# 10_-FLASH_SD.net
KiCad netlist of a schematic drawn in Altium Designer
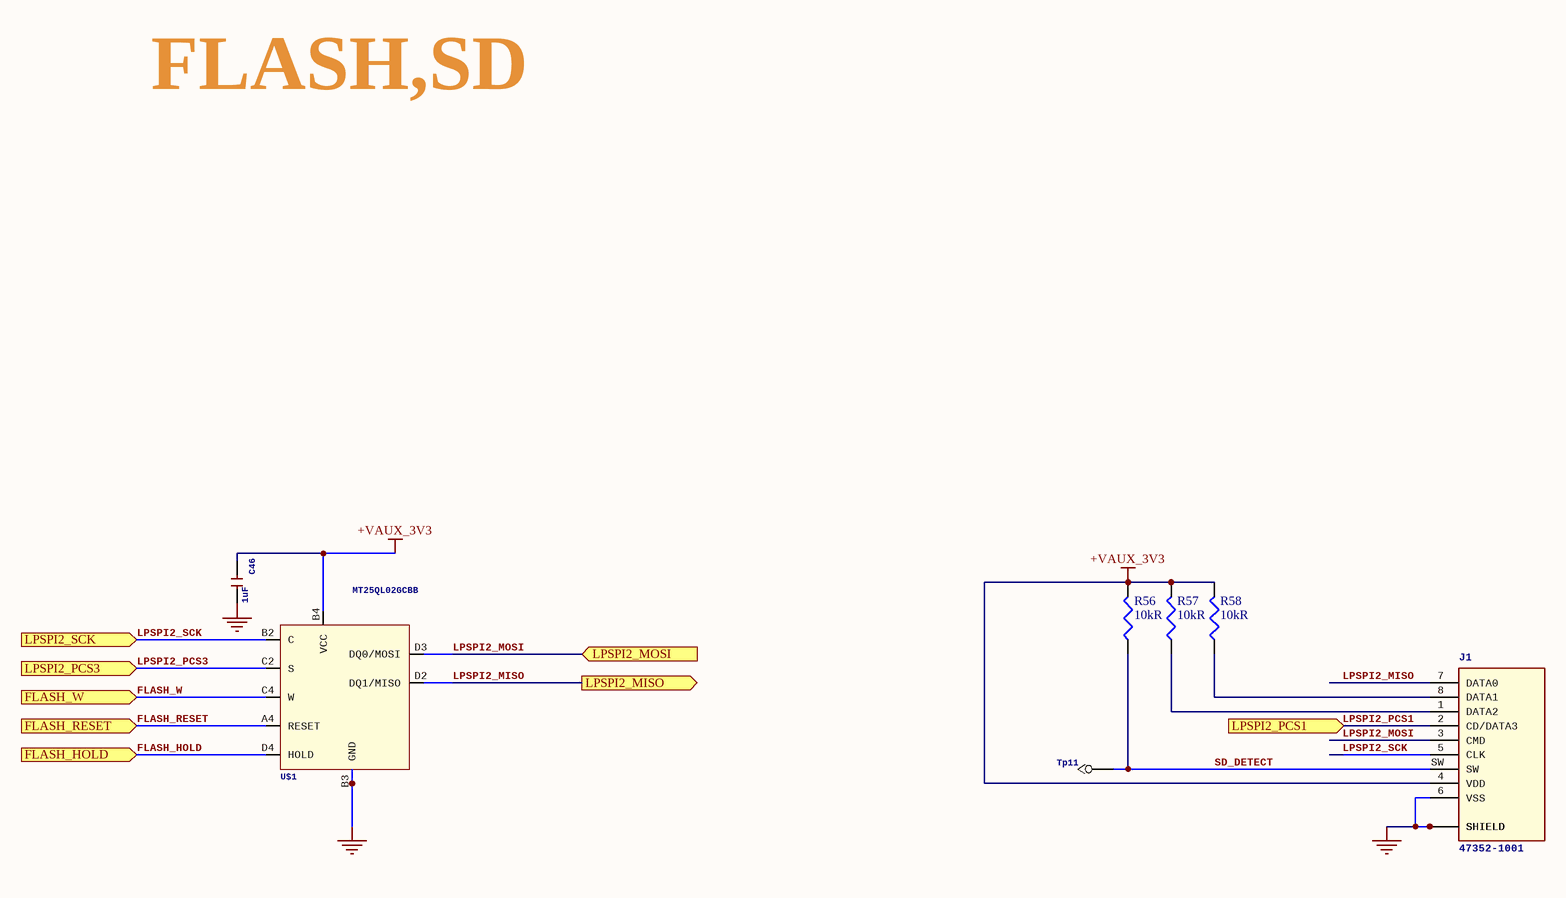
[diagram p0: [10]-FLASH,SD.SchDoc]

(export (version "E")
  (design (tool "Eeschema 10.0.6"))
  (components
    (comp (ref "C46")
      (value "1uF")
      (footprint "C0805")
      (description "302010165")
      (fields (field (name "MPN") "CC0805KRX7R9BB104") (field (name "LIBRARYNAME") "Seeed-Capacitor"))
      (libsource (lib "Seeed-Capacitor") (part "CERAMIC-100NF-50V-10%-X7R(0805)"))
    )
    (comp (ref "J1")
      (value "47352-1001")
      (footprint "MOLEX_47352-1001")
      (fields (field (name "MF") "Molex"))
      (libsource (lib "WeOnReferenceBoard") (part "47352-1001"))
    )
    (comp (ref "R56")
      (value "ERJ-2GEJ103X")
      (footprint "RES0402")
      (description "Res Thick Film 0402 10K Ohm 5% 1/10W ±200ppm/°C Molded SMD SMD Punched Carrier T/R")
      (fields
        (field (name "MANUFACTURER") "Panasonic")
        (field (name "TOLERANCE") "5%")
        (field (name "RESISTANCE") "10kR")
      )
      (libsource (lib "WeOnReferenceBoard") (part "ERJ-2GEJ103X"))
    )
    (comp (ref "R57")
      (value "ERJ-2GEJ103X")
      (footprint "RES0402")
      (description "Res Thick Film 0402 10K Ohm 5% 1/10W ±200ppm/°C Molded SMD SMD Punched Carrier T/R")
      (fields
        (field (name "MANUFACTURER") "Panasonic")
        (field (name "TOLERANCE") "5%")
        (field (name "RESISTANCE") "10kR")
      )
      (libsource (lib "WeOnReferenceBoard") (part "ERJ-2GEJ103X"))
    )
    (comp (ref "R58")
      (value "ERJ-2GEJ103X")
      (footprint "RES0402")
      (description "Res Thick Film 0402 10K Ohm 5% 1/10W ±200ppm/°C Molded SMD SMD Punched Carrier T/R")
      (fields
        (field (name "MANUFACTURER") "Panasonic")
        (field (name "TOLERANCE") "5%")
        (field (name "RESISTANCE") "10kR")
      )
      (libsource (lib "WeOnReferenceBoard") (part "ERJ-2GEJ103X"))
    )
    (comp (ref "Tp11")
      (value "TP")
      (footprint "TestPoint")
      (libsource (lib "altium-import") (part "root_2_TP_"))
    )
    (comp (ref "U$1")
      (value "MT25QL02GCBB")
      (footprint "BGA24C100P5X5_600X800X155")
      (libsource (lib "WeOnReferenceBoard") (part "MT25QL02GCBB"))
    )
  )
  (nets
    (net (code "1") (name "+VAUX_3V3") (class "Default")
      (node (ref "C46") (pin "1") (pinfunction "1_1") (pintype "passive"))
      (node (ref "J1") (pin "4") (pinfunction "VDD_4") (pintype "passive"))
      (node (ref "R56") (pin "2") (pinfunction "2_2") (pintype "passive"))
      (node (ref "R57") (pin "2") (pinfunction "2_2") (pintype "passive"))
      (node (ref "R58") (pin "2") (pinfunction "2_2") (pintype "passive"))
      (node (ref "U$1") (pin "B4") (pinfunction "VCC_B4") (pintype "passive"))
    )
    (net (code "2") (name "/FLASH_HOLD") (class "Default")
      (node (ref "U$1") (pin "D4") (pinfunction "HOLD_D4") (pintype "passive"))
    )
    (net (code "3") (name "/FLASH_RESET") (class "Default")
      (node (ref "U$1") (pin "A4") (pinfunction "RESET_A4") (pintype "passive"))
    )
    (net (code "4") (name "/FLASH_W") (class "Default")
      (node (ref "U$1") (pin "C4") (pinfunction "W_C4") (pintype "passive"))
    )
    (net (code "5") (name "/LPSPI2_MISO") (class "Default")
      (node (ref "J1") (pin "7") (pinfunction "DATA0_7") (pintype "passive"))
      (node (ref "U$1") (pin "D2") (pinfunction "DQ1/MISO_D2") (pintype "passive"))
    )
    (net (code "6") (name "/LPSPI2_MOSI") (class "Default")
      (node (ref "J1") (pin "3") (pinfunction "CMD_3") (pintype "passive"))
      (node (ref "U$1") (pin "D3") (pinfunction "DQ0/MOSI_D3") (pintype "passive"))
    )
    (net (code "7") (name "/LPSPI2_PCS1") (class "Default")
      (node (ref "J1") (pin "2") (pinfunction "CD/DATA3_2") (pintype "passive"))
    )
    (net (code "8") (name "/LPSPI2_PCS3") (class "Default")
      (node (ref "U$1") (pin "C2") (pinfunction "S_C2") (pintype "passive"))
    )
    (net (code "9") (name "/LPSPI2_SCK") (class "Default")
      (node (ref "J1") (pin "5") (pinfunction "CLK_5") (pintype "passive"))
      (node (ref "U$1") (pin "B2") (pinfunction "C_B2") (pintype "passive"))
    )
    (net (code "10") (name "/SD_DETECT") (class "Default")
      (node (ref "J1") (pin "SW") (pinfunction "SW_SW") (pintype "passive"))
      (node (ref "R56") (pin "1") (pinfunction "1_1") (pintype "passive"))
      (node (ref "Tp11") (pin "1") (pinfunction "1_1") (pintype "passive"))
    )
    (net (code "11") (name "GND") (class "Default")
      (node (ref "C46") (pin "2") (pinfunction "2_2") (pintype "passive"))
      (node (ref "J1") (pin "6") (pinfunction "VSS_6") (pintype "passive"))
      (node (ref "J1") (pin "S1") (pinfunction "SHIELD_S1") (pintype "passive"))
      (node (ref "J1") (pin "S2") (pinfunction "SHIELD_S2") (pintype "passive"))
      (node (ref "J1") (pin "S3") (pinfunction "SHIELD_S3") (pintype "passive"))
      (node (ref "J1") (pin "S4") (pinfunction "SHIELD_S4") (pintype "passive"))
      (node (ref "U$1") (pin "B3") (pinfunction "GND_B3") (pintype "passive"))
    )
    (net (code "12") (name "Net-(J1-DATA1)") (class "Default")
      (node (ref "J1") (pin "8") (pinfunction "DATA1_8") (pintype "passive"))
      (node (ref "R58") (pin "1") (pinfunction "1_1") (pintype "passive"))
    )
    (net (code "13") (name "Net-(J1-DATA2)") (class "Default")
      (node (ref "J1") (pin "1") (pinfunction "DATA2_1") (pintype "passive"))
      (node (ref "R57") (pin "1") (pinfunction "1_1") (pintype "passive"))
    )
  )
)
